# LED_Driver_-_1.net
KiCad netlist of a schematic drawn in Altium Designer
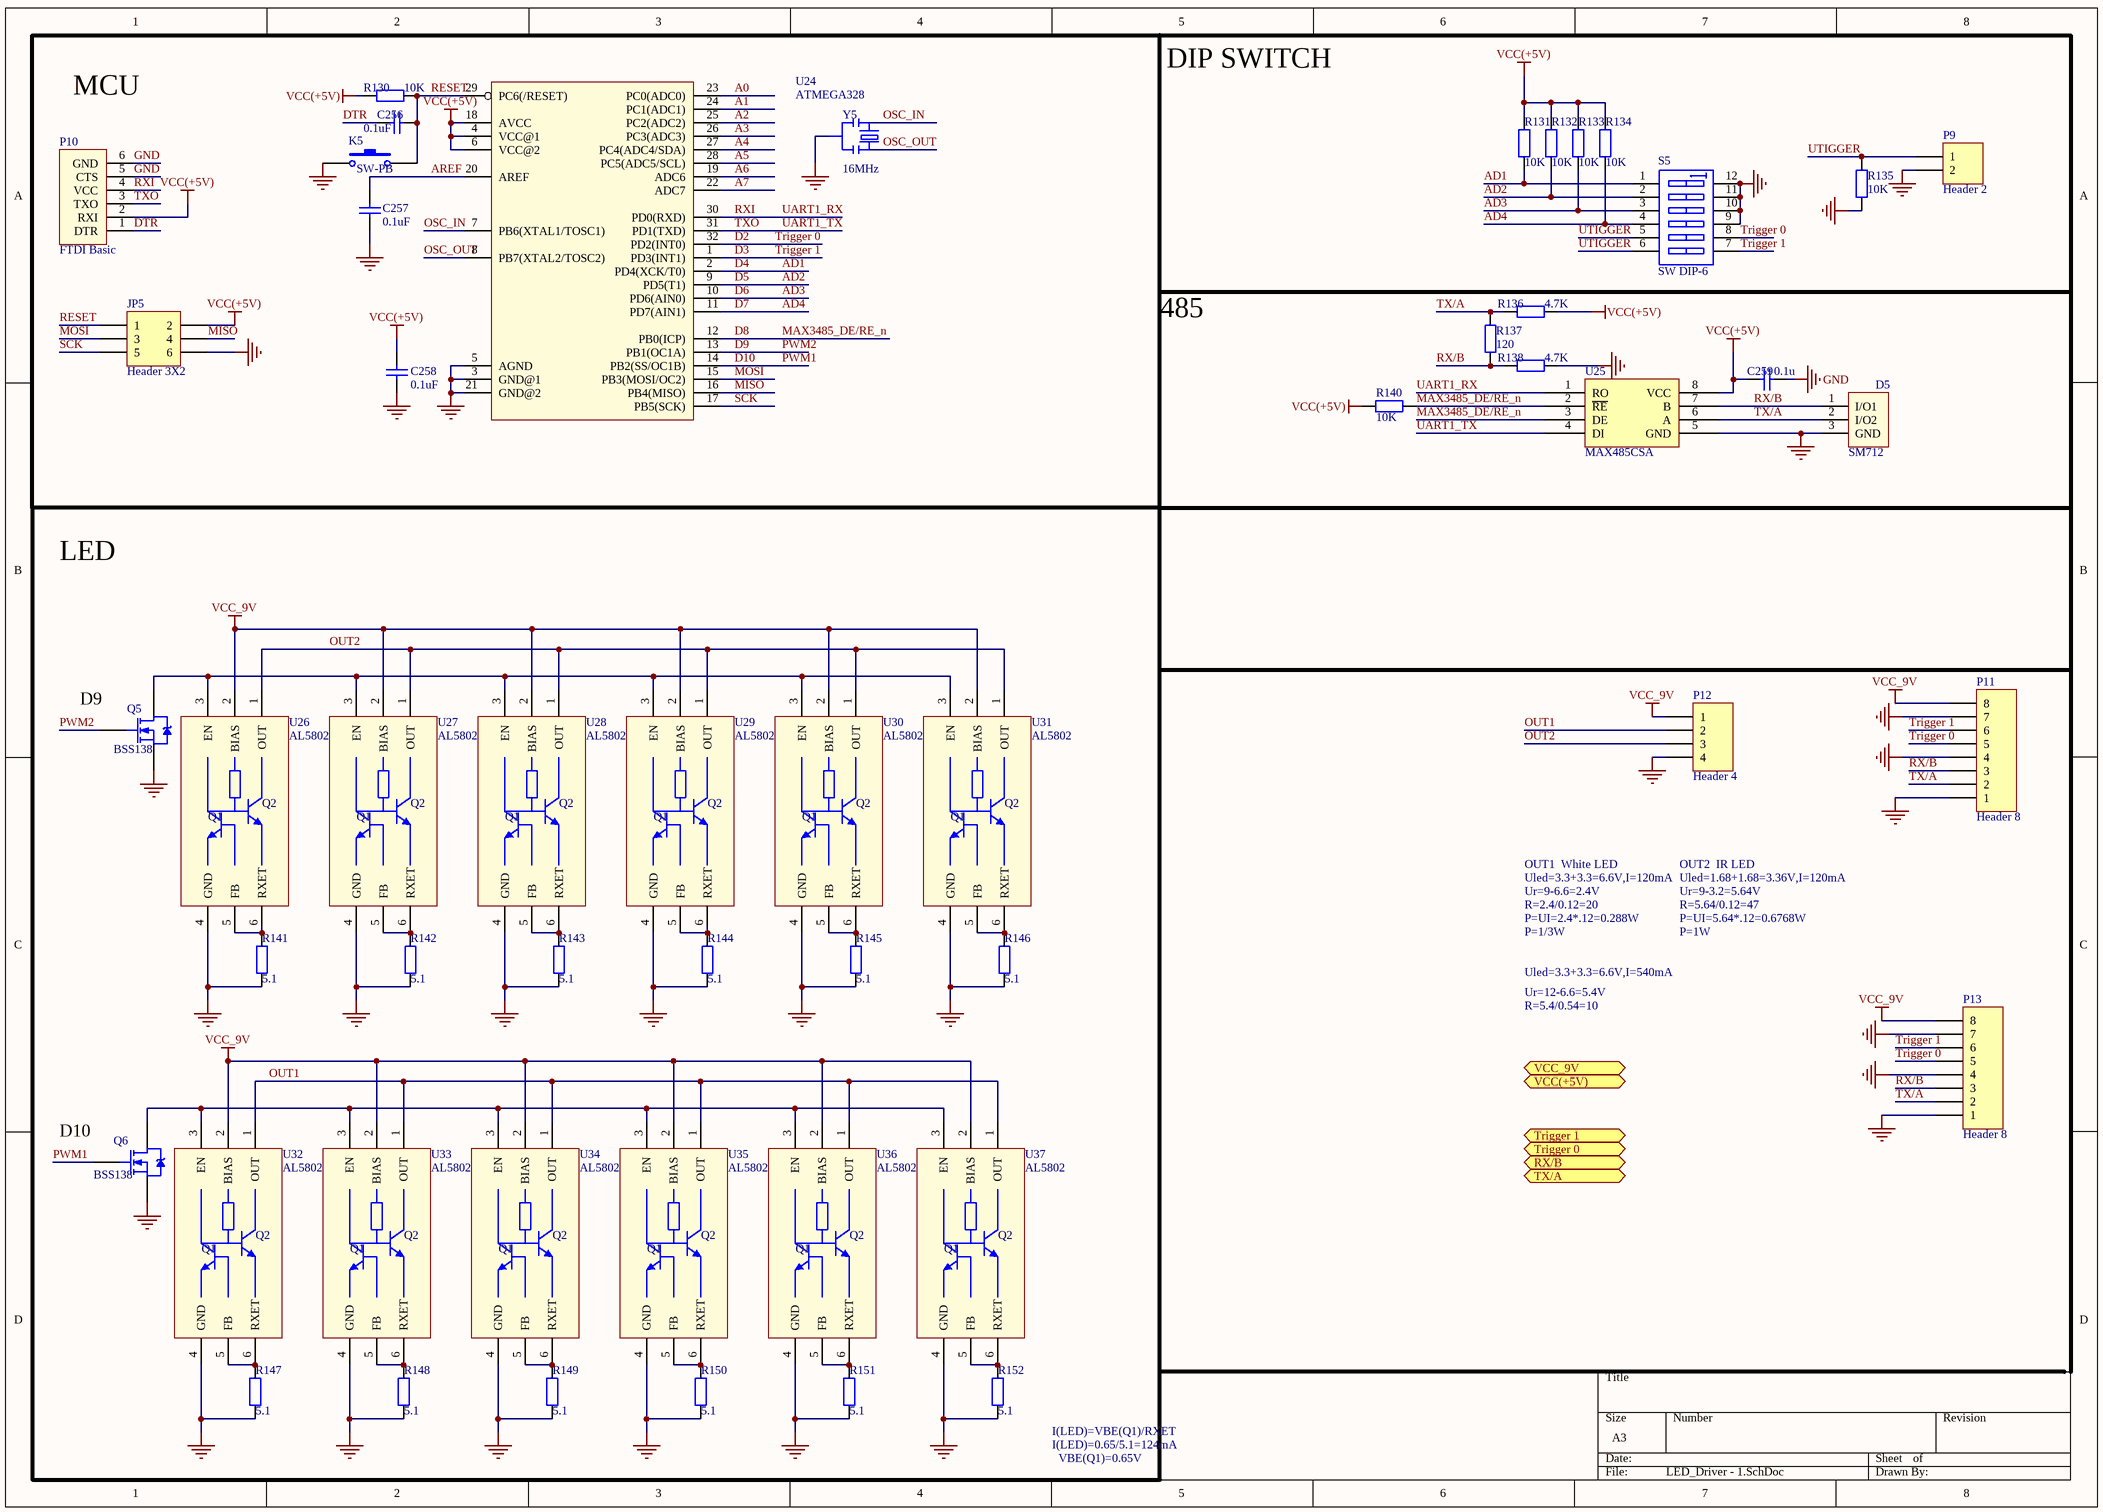
[diagram p0: LED_Driver - 1.SchDoc]

(export (version "E")
  (design (tool "Eeschema 10.0.6"))
  (components
    (comp (ref "C256")
      (value "0.1uF")
      (footprint "C0603")
      (description "Capacitor")
      (fields (field (name "IPARTNUMBER") "C100nF25V10%X7R") (field (name "VOLTAGE") "25V"))
      (libsource (lib "Schlib1") (part "CAP SMT C100nF25V10%X7R"))
    )
    (comp (ref "C257")
      (value "0.1uF")
      (footprint "C0603")
      (description "Capacitor")
      (fields (field (name "IPARTNUMBER") "C100nF25V10%X7R") (field (name "VOLTAGE") "25V"))
      (libsource (lib "Schlib1") (part "CAP SMT C100nF25V10%X7R"))
    )
    (comp (ref "C258")
      (value "0.1uF")
      (footprint "C0603")
      (description "Capacitor")
      (fields (field (name "IPARTNUMBER") "C100nF25V10%X7R") (field (name "VOLTAGE") "25V"))
      (libsource (lib "Schlib1") (part "CAP SMT C100nF25V10%X7R"))
    )
    (comp (ref "C259")
      (value "0.1u")
      (footprint "C0603")
      (description "Capacitor")
      (fields (field (name "PUBLISHER") "Altium Limited"))
      (libsource (lib "Miscellaneous Devices") (part "Cap"))
    )
    (comp (ref "D5")
      (value "SM712")
      (footprint "SOT23-3")
      (libsource (lib "STM32F4_CAM V2.0") (part "SM712"))
    )
    (comp (ref "JP5")
      (value "Header 3X2")
      (footprint "MHDR1X6")
      (description "Header, 3-Pin, Dual row")
      (fields (field (name "PUBLISHER") "Altium Limited"))
      (libsource (lib "Miscellaneous Connectors") (part "Header 3X2"))
    )
    (comp (ref "K5")
      (value "SW-PB")
      (footprint "157SW")
      (description "Switch")
      (fields (field (name "PUBLISHER") "Altium Limited"))
      (libsource (lib "Miscellaneous Devices") (part "SW-PB"))
    )
    (comp (ref "P9")
      (value "Header 2")
      (footprint "HDR1X2")
      (description "Header, 2-Pin")
      (fields (field (name "PUBLISHER") "Altium Limited"))
      (libsource (lib "Miscellaneous Connectors") (part "Header 2"))
    )
    (comp (ref "P10")
      (value "FTDI Basic")
      (footprint "MHDR1X6")
      (libsource (lib "PCB_Project1") (part "ARDUINO_SERIAL_PROGRAMPTH"))
    )
    (comp (ref "P11")
      (value "Header 8")
      (footprint "SH_1.25MM*8")
      (description "Header, 8-Pin")
      (fields (field (name "PUBLISHER") "Altium Limited"))
      (libsource (lib "Miscellaneous Connectors") (part "Header 8"))
    )
    (comp (ref "P12")
      (value "Header 4")
      (footprint "SMT_1.25MM*4")
      (description "Header, 4-Pin")
      (fields (field (name "PUBLISHER") "Altium Limited"))
      (libsource (lib "Miscellaneous Connectors") (part "Header 4"))
    )
    (comp (ref "P13")
      (value "Header 8")
      (footprint "SH_1.25MM*8")
      (description "Header, 8-Pin")
      (fields (field (name "PUBLISHER") "Altium Limited"))
      (libsource (lib "Miscellaneous Connectors") (part "Header 8"))
    )
    (comp (ref "Q5")
      (value "BSS138")
      (footprint "SOT-23 (Standard)")
      (fields
        (field (name "MANUFACTURER") "Fairchild Semiconductor")
        (field (name "MANUFACTURER PART NUMBER") "BSS123")
      )
      (libsource (lib "Miscellaneous_Devices") (part "NMOS"))
    )
    (comp (ref "Q6")
      (value "BSS138")
      (footprint "SOT-23 (Standard)")
      (fields
        (field (name "MANUFACTURER") "Fairchild Semiconductor")
        (field (name "MANUFACTURER PART NUMBER") "BSS123")
      )
      (libsource (lib "Miscellaneous_Devices") (part "NMOS"))
    )
    (comp (ref "R130")
      (value "10K")
      (footprint "R0603")
      (description "Resistor")
      (libsource (lib "") (part "Res2_2"))
    )
    (comp (ref "R131")
      (value "10K")
      (footprint "R0603")
      (description "Resistor")
      (libsource (lib "") (part "Res2_1"))
    )
    (comp (ref "R132")
      (value "10K")
      (footprint "R0603")
      (description "Resistor")
      (libsource (lib "") (part "Res2_1"))
    )
    (comp (ref "R133")
      (value "10K")
      (footprint "R0603")
      (description "Resistor")
      (libsource (lib "") (part "Res2_1"))
    )
    (comp (ref "R134")
      (value "10K")
      (footprint "R0603")
      (description "Resistor")
      (libsource (lib "") (part "Res2_1"))
    )
    (comp (ref "R135")
      (value "10K")
      (footprint "R0603")
      (description "Resistor")
      (fields (field (name "PUBLISHER") "Altium Limited"))
      (libsource (lib "Miscellaneous Devices") (part "Res2"))
    )
    (comp (ref "R136")
      (value "4.7K")
      (footprint "R0603")
      (description "Resistor")
      (libsource (lib "DM642") (part "Res2"))
    )
    (comp (ref "R137")
      (value "120")
      (footprint "R0603")
      (description "Resistor")
      (libsource (lib "") (part "Res2_1"))
    )
    (comp (ref "R138")
      (value "4.7K")
      (footprint "R0603")
      (description "Resistor")
      (libsource (lib "DM642") (part "Res2"))
    )
    (comp (ref "R140")
      (value "10K")
      (footprint "R0603")
      (description "Resistor")
      (libsource (lib "DM642") (part "Res2"))
    )
    (comp (ref "R141")
      (value "5.1")
      (footprint "R0603")
      (description "Resistor")
      (libsource (lib "") (part "Res2_1"))
    )
    (comp (ref "R142")
      (value "5.1")
      (footprint "R0603")
      (description "Resistor")
      (libsource (lib "") (part "Res2_1"))
    )
    (comp (ref "R143")
      (value "5.1")
      (footprint "R0603")
      (description "Resistor")
      (libsource (lib "") (part "Res2_1"))
    )
    (comp (ref "R144")
      (value "5.1")
      (footprint "R0603")
      (description "Resistor")
      (libsource (lib "") (part "Res2_1"))
    )
    (comp (ref "R145")
      (value "5.1")
      (footprint "R0603")
      (description "Resistor")
      (libsource (lib "") (part "Res2_1"))
    )
    (comp (ref "R146")
      (value "5.1")
      (footprint "R0603")
      (description "Resistor")
      (libsource (lib "") (part "Res2_1"))
    )
    (comp (ref "R147")
      (value "5.1")
      (footprint "R0603")
      (description "Resistor")
      (libsource (lib "") (part "Res2_1"))
    )
    (comp (ref "R148")
      (value "5.1")
      (footprint "R0603")
      (description "Resistor")
      (libsource (lib "") (part "Res2_1"))
    )
    (comp (ref "R149")
      (value "5.1")
      (footprint "R0603")
      (description "Resistor")
      (libsource (lib "") (part "Res2_1"))
    )
    (comp (ref "R150")
      (value "5.1")
      (footprint "R0603")
      (description "Resistor")
      (libsource (lib "") (part "Res2_1"))
    )
    (comp (ref "R151")
      (value "5.1")
      (footprint "R0603")
      (description "Resistor")
      (libsource (lib "") (part "Res2_1"))
    )
    (comp (ref "R152")
      (value "5.1")
      (footprint "R0603")
      (description "Resistor")
      (libsource (lib "") (part "Res2_1"))
    )
    (comp (ref "S5")
      (value "SW DIP-6")
      (footprint "DIP_SW_6WAY_SMD")
      (description "DIP Switch, 6 Position, SPST")
      (fields (field (name "PUBLISHER") "Altium Limited"))
      (libsource (lib "Miscellaneous Devices") (part "SW DIP-6"))
    )
    (comp (ref "U24")
      (value "ATMEGA328")
      (footprint "TQFP32-08")
      (libsource (lib "PCB_Project1") (part "ATMEGA168"))
    )
    (comp (ref "U25")
      (value "MAX485CSA")
      (footprint "SOIC-8")
      (libsource (lib "STM32F4_CAM V1.2") (part "MAX3485CSA"))
    )
    (comp (ref "U26") (value "AL5802") (footprint "SOT26") (libsource (lib "LED") (part "AL5802")))
    (comp (ref "U27") (value "AL5802") (footprint "SOT26") (libsource (lib "LED") (part "AL5802")))
    (comp (ref "U28") (value "AL5802") (footprint "SOT26") (libsource (lib "LED") (part "AL5802")))
    (comp (ref "U29") (value "AL5802") (footprint "SOT26") (libsource (lib "LED") (part "AL5802")))
    (comp (ref "U30") (value "AL5802") (footprint "SOT26") (libsource (lib "LED") (part "AL5802")))
    (comp (ref "U31") (value "AL5802") (footprint "SOT26") (libsource (lib "LED") (part "AL5802")))
    (comp (ref "U32") (value "AL5802") (footprint "SOT26") (libsource (lib "LED") (part "AL5802")))
    (comp (ref "U33") (value "AL5802") (footprint "SOT26") (libsource (lib "LED") (part "AL5802")))
    (comp (ref "U34") (value "AL5802") (footprint "SOT26") (libsource (lib "LED") (part "AL5802")))
    (comp (ref "U35") (value "AL5802") (footprint "SOT26") (libsource (lib "LED") (part "AL5802")))
    (comp (ref "U36") (value "AL5802") (footprint "SOT26") (libsource (lib "LED") (part "AL5802")))
    (comp (ref "U37") (value "AL5802") (footprint "SOT26") (libsource (lib "LED") (part "AL5802")))
    (comp (ref "Y5")
      (value "16MHz")
      (footprint "RESONATOR-SMD")
      (libsource (lib "SparkFun") (part "RESONATORSMD"))
    )
  )
  (nets
    (net (code "1") (name "/A0") (class "Default")
      (node (ref "U24") (pin "23") (pinfunction "PC0(ADC0)_23") (pintype "passive"))
    )
    (net (code "2") (name "/A1") (class "Default")
      (node (ref "U24") (pin "24") (pinfunction "PC1(ADC1)_24") (pintype "passive"))
    )
    (net (code "3") (name "/A2") (class "Default")
      (node (ref "U24") (pin "25") (pinfunction "PC2(ADC2)_25") (pintype "passive"))
    )
    (net (code "4") (name "/A3") (class "Default")
      (node (ref "U24") (pin "26") (pinfunction "PC3(ADC3)_26") (pintype "passive"))
    )
    (net (code "5") (name "/A4") (class "Default")
      (node (ref "U24") (pin "27") (pinfunction "PC4(ADC4/SDA)_27") (pintype "passive"))
    )
    (net (code "6") (name "/A5") (class "Default")
      (node (ref "U24") (pin "28") (pinfunction "PC5(ADC5/SCL)_28") (pintype "passive"))
    )
    (net (code "7") (name "/A6") (class "Default")
      (node (ref "U24") (pin "19") (pinfunction "ADC6_19") (pintype "passive"))
    )
    (net (code "8") (name "/A7") (class "Default")
      (node (ref "U24") (pin "22") (pinfunction "ADC7_22") (pintype "passive"))
    )
    (net (code "9") (name "/AD1") (class "Default")
      (node (ref "R131") (pin "2") (pinfunction "2_2") (pintype "passive"))
      (node (ref "S5") (pin "1") (pinfunction "A1_1") (pintype "passive"))
      (node (ref "U24") (pin "2") (pinfunction "PD4(XCK/T0)_2") (pintype "passive"))
    )
    (net (code "10") (name "/AD2") (class "Default")
      (node (ref "R132") (pin "2") (pinfunction "2_2") (pintype "passive"))
      (node (ref "S5") (pin "2") (pinfunction "A2_2") (pintype "passive"))
      (node (ref "U24") (pin "9") (pinfunction "PD5(T1)_9") (pintype "passive"))
    )
    (net (code "11") (name "/AD3") (class "Default")
      (node (ref "R133") (pin "2") (pinfunction "2_2") (pintype "passive"))
      (node (ref "S5") (pin "3") (pinfunction "A3_3") (pintype "passive"))
      (node (ref "U24") (pin "10") (pinfunction "PD6(AIN0)_10") (pintype "passive"))
    )
    (net (code "12") (name "/AD4") (class "Default")
      (node (ref "R134") (pin "2") (pinfunction "2_2") (pintype "passive"))
      (node (ref "S5") (pin "4") (pinfunction "A4_4") (pintype "passive"))
      (node (ref "U24") (pin "11") (pinfunction "PD7(AIN1)_11") (pintype "passive"))
    )
    (net (code "13") (name "/AREF") (class "Default")
      (node (ref "C257") (pin "2") (pinfunction "2_2") (pintype "passive"))
      (node (ref "U24") (pin "20") (pinfunction "AREF_20") (pintype "passive"))
    )
    (net (code "14") (name "/D2") (class "Default")
      (node (ref "P11") (pin "5") (pinfunction "5_5") (pintype "passive"))
      (node (ref "P13") (pin "5") (pinfunction "5_5") (pintype "passive"))
      (node (ref "S5") (pin "8") (pinfunction "B5_8") (pintype "passive"))
      (node (ref "U24") (pin "32") (pinfunction "PD2(INT0)_32") (pintype "passive"))
    )
    (net (code "15") (name "/D3") (class "Default")
      (node (ref "P11") (pin "6") (pinfunction "6_6") (pintype "passive"))
      (node (ref "P13") (pin "6") (pinfunction "6_6") (pintype "passive"))
      (node (ref "S5") (pin "7") (pinfunction "B6_7") (pintype "passive"))
      (node (ref "U24") (pin "1") (pinfunction "PD3(INT1)_1") (pintype "passive"))
    )
    (net (code "16") (name "/D8") (class "Default")
      (node (ref "R140") (pin "1") (pinfunction "1_1") (pintype "passive"))
      (node (ref "U24") (pin "12") (pinfunction "PB0(ICP)_12") (pintype "passive"))
      (node (ref "U25") (pin "2") (pinfunction "~{RE}_2") (pintype "passive"))
      (node (ref "U25") (pin "3") (pinfunction "DE_3") (pintype "passive"))
    )
    (net (code "17") (name "/D9") (class "Default")
      (node (ref "Q5") (pin "G") (pinfunction "G_G") (pintype "passive"))
      (node (ref "U24") (pin "13") (pinfunction "PB1(OC1A)_13") (pintype "passive"))
    )
    (net (code "18") (name "/D10") (class "Default")
      (node (ref "Q6") (pin "G") (pinfunction "G_G") (pintype "passive"))
      (node (ref "U24") (pin "14") (pinfunction "PB2(SS/OC1B)_14") (pintype "passive"))
    )
    (net (code "19") (name "/DTR") (class "Default")
      (node (ref "C256") (pin "1") (pinfunction "1_1") (pintype "passive"))
      (node (ref "P10") (pin "1") (pinfunction "DTR_1") (pintype "passive"))
    )
    (net (code "20") (name "/MISO") (class "Default")
      (node (ref "JP5") (pin "4") (pinfunction "4_4") (pintype "passive"))
      (node (ref "U24") (pin "16") (pinfunction "PB4(MISO)_16") (pintype "passive"))
    )
    (net (code "21") (name "/MOSI") (class "Default")
      (node (ref "JP5") (pin "3") (pinfunction "3_3") (pintype "passive"))
      (node (ref "U24") (pin "15") (pinfunction "PB3(MOSI/OC2)_15") (pintype "passive"))
    )
    (net (code "22") (name "/OSC_IN") (class "Default")
      (node (ref "U24") (pin "7") (pinfunction "PB6(XTAL1/TOSC1)_7") (pintype "passive"))
      (node (ref "Y5") (pin "3") (pinfunction "3_3") (pintype "passive"))
    )
    (net (code "23") (name "/OSC_OUT") (class "Default")
      (node (ref "U24") (pin "8") (pinfunction "PB7(XTAL2/TOSC2)_8") (pintype "passive"))
      (node (ref "Y5") (pin "1") (pinfunction "1_1") (pintype "passive"))
    )
    (net (code "24") (name "/OUT1") (class "Default")
      (node (ref "P12") (pin "2") (pinfunction "2_2") (pintype "passive"))
      (node (ref "U32") (pin "1") (pinfunction "OUT_1") (pintype "passive"))
      (node (ref "U33") (pin "1") (pinfunction "OUT_1") (pintype "passive"))
      (node (ref "U34") (pin "1") (pinfunction "OUT_1") (pintype "passive"))
      (node (ref "U35") (pin "1") (pinfunction "OUT_1") (pintype "passive"))
      (node (ref "U36") (pin "1") (pinfunction "OUT_1") (pintype "passive"))
      (node (ref "U37") (pin "1") (pinfunction "OUT_1") (pintype "passive"))
    )
    (net (code "25") (name "/OUT2") (class "Default")
      (node (ref "P12") (pin "3") (pinfunction "3_3") (pintype "passive"))
      (node (ref "U26") (pin "1") (pinfunction "OUT_1") (pintype "passive"))
      (node (ref "U27") (pin "1") (pinfunction "OUT_1") (pintype "passive"))
      (node (ref "U28") (pin "1") (pinfunction "OUT_1") (pintype "passive"))
      (node (ref "U29") (pin "1") (pinfunction "OUT_1") (pintype "passive"))
      (node (ref "U30") (pin "1") (pinfunction "OUT_1") (pintype "passive"))
      (node (ref "U31") (pin "1") (pinfunction "OUT_1") (pintype "passive"))
    )
    (net (code "26") (name "/RESET") (class "Default")
      (node (ref "C256") (pin "2") (pinfunction "2_2") (pintype "passive"))
      (node (ref "JP5") (pin "1") (pinfunction "1_1") (pintype "passive"))
      (node (ref "K5") (pin "2") (pinfunction "2_2") (pintype "passive"))
      (node (ref "R130") (pin "2") (pinfunction "2_2") (pintype "passive"))
      (node (ref "U24") (pin "29") (pinfunction "PC6(/RESET)_29") (pintype "passive"))
    )
    (net (code "27") (name "/RXI") (class "Default")
      (node (ref "P10") (pin "4") (pinfunction "VCC_4") (pintype "passive"))
      (node (ref "U24") (pin "30") (pinfunction "PD0(RXD)_30") (pintype "passive"))
      (node (ref "U25") (pin "1") (pinfunction "RO_1") (pintype "passive"))
    )
    (net (code "28") (name "/RX{slash}B") (class "Default")
      (node (ref "D5") (pin "1") (pinfunction "I/O1_1") (pintype "passive"))
      (node (ref "P11") (pin "3") (pinfunction "3_3") (pintype "passive"))
      (node (ref "P13") (pin "3") (pinfunction "3_3") (pintype "passive"))
      (node (ref "R137") (pin "2") (pinfunction "2_2") (pintype "passive"))
      (node (ref "R138") (pin "2") (pinfunction "2_2") (pintype "passive"))
      (node (ref "U25") (pin "7") (pinfunction "B_7") (pintype "passive"))
    )
    (net (code "29") (name "/SCK") (class "Default")
      (node (ref "JP5") (pin "5") (pinfunction "5_5") (pintype "passive"))
      (node (ref "U24") (pin "17") (pinfunction "PB5(SCK)_17") (pintype "passive"))
    )
    (net (code "30") (name "/TXO") (class "Default")
      (node (ref "P10") (pin "3") (pinfunction "TXO_3") (pintype "passive"))
      (node (ref "U24") (pin "31") (pinfunction "PD1(TXD)_31") (pintype "passive"))
      (node (ref "U25") (pin "4") (pinfunction "DI_4") (pintype "passive"))
    )
    (net (code "31") (name "/TX{slash}A") (class "Default")
      (node (ref "D5") (pin "2") (pinfunction "I/O2_2") (pintype "passive"))
      (node (ref "P11") (pin "2") (pinfunction "2_2") (pintype "passive"))
      (node (ref "P13") (pin "2") (pinfunction "2_2") (pintype "passive"))
      (node (ref "R136") (pin "2") (pinfunction "2_2") (pintype "passive"))
      (node (ref "R137") (pin "1") (pinfunction "1_1") (pintype "passive"))
      (node (ref "U25") (pin "6") (pinfunction "A_6") (pintype "passive"))
    )
    (net (code "32") (name "/UTIGGER") (class "Default")
      (node (ref "P9") (pin "1") (pinfunction "1_1") (pintype "passive"))
      (node (ref "R135") (pin "2") (pinfunction "2_2") (pintype "passive"))
      (node (ref "S5") (pin "5") (pinfunction "A5_5") (pintype "passive"))
      (node (ref "S5") (pin "6") (pinfunction "A6_6") (pintype "passive"))
    )
    (net (code "33") (name "GND") (class "Default")
      (node (ref "C257") (pin "1") (pinfunction "1_1") (pintype "passive"))
      (node (ref "C258") (pin "2") (pinfunction "2_2") (pintype "passive"))
      (node (ref "C259") (pin "1") (pinfunction "1_1") (pintype "passive"))
      (node (ref "D5") (pin "3") (pinfunction "GND_3") (pintype "passive"))
      (node (ref "JP5") (pin "6") (pinfunction "6_6") (pintype "passive"))
      (node (ref "K5") (pin "1") (pinfunction "1_1") (pintype "passive"))
      (node (ref "P10") (pin "5") (pinfunction "CTS_5") (pintype "passive"))
      (node (ref "P10") (pin "6") (pinfunction "GND_6") (pintype "passive"))
      (node (ref "P11") (pin "1") (pinfunction "1_1") (pintype "passive"))
      (node (ref "P11") (pin "4") (pinfunction "4_4") (pintype "passive"))
      (node (ref "P11") (pin "7") (pinfunction "7_7") (pintype "passive"))
      (node (ref "P12") (pin "4") (pinfunction "4_4") (pintype "passive"))
      (node (ref "P13") (pin "1") (pinfunction "1_1") (pintype "passive"))
      (node (ref "P13") (pin "4") (pinfunction "4_4") (pintype "passive"))
      (node (ref "P13") (pin "7") (pinfunction "7_7") (pintype "passive"))
      (node (ref "P9") (pin "2") (pinfunction "2_2") (pintype "passive"))
      (node (ref "Q5") (pin "S") (pinfunction "S_S") (pintype "passive"))
      (node (ref "Q6") (pin "S") (pinfunction "S_S") (pintype "passive"))
      (node (ref "R135") (pin "1") (pinfunction "1_1") (pintype "passive"))
      (node (ref "R138") (pin "1") (pinfunction "1_1") (pintype "passive"))
      (node (ref "R141") (pin "2") (pinfunction "2_2") (pintype "passive"))
      (node (ref "R142") (pin "2") (pinfunction "2_2") (pintype "passive"))
      (node (ref "R143") (pin "2") (pinfunction "2_2") (pintype "passive"))
      (node (ref "R144") (pin "2") (pinfunction "2_2") (pintype "passive"))
      (node (ref "R145") (pin "2") (pinfunction "2_2") (pintype "passive"))
      (node (ref "R146") (pin "2") (pinfunction "2_2") (pintype "passive"))
      (node (ref "R147") (pin "2") (pinfunction "2_2") (pintype "passive"))
      (node (ref "R148") (pin "2") (pinfunction "2_2") (pintype "passive"))
      (node (ref "R149") (pin "2") (pinfunction "2_2") (pintype "passive"))
      (node (ref "R150") (pin "2") (pinfunction "2_2") (pintype "passive"))
      (node (ref "R151") (pin "2") (pinfunction "2_2") (pintype "passive"))
      (node (ref "R152") (pin "2") (pinfunction "2_2") (pintype "passive"))
      (node (ref "S5") (pin "10") (pinfunction "B3_10") (pintype "passive"))
      (node (ref "S5") (pin "11") (pinfunction "B2_11") (pintype "passive"))
      (node (ref "S5") (pin "12") (pinfunction "B1_12") (pintype "passive"))
      (node (ref "S5") (pin "9") (pinfunction "B4_9") (pintype "passive"))
      (node (ref "U24") (pin "21") (pinfunction "GND@2_21") (pintype "passive"))
      (node (ref "U24") (pin "3") (pinfunction "GND@1_3") (pintype "passive"))
      (node (ref "U24") (pin "5") (pinfunction "AGND_5") (pintype "passive"))
      (node (ref "U25") (pin "5") (pinfunction "GND_5") (pintype "passive"))
      (node (ref "U26") (pin "4") (pinfunction "GND_4") (pintype "passive"))
      (node (ref "U27") (pin "4") (pinfunction "GND_4") (pintype "passive"))
      (node (ref "U28") (pin "4") (pinfunction "GND_4") (pintype "passive"))
      (node (ref "U29") (pin "4") (pinfunction "GND_4") (pintype "passive"))
      (node (ref "U30") (pin "4") (pinfunction "GND_4") (pintype "passive"))
      (node (ref "U31") (pin "4") (pinfunction "GND_4") (pintype "passive"))
      (node (ref "U32") (pin "4") (pinfunction "GND_4") (pintype "passive"))
      (node (ref "U33") (pin "4") (pinfunction "GND_4") (pintype "passive"))
      (node (ref "U34") (pin "4") (pinfunction "GND_4") (pintype "passive"))
      (node (ref "U35") (pin "4") (pinfunction "GND_4") (pintype "passive"))
      (node (ref "U36") (pin "4") (pinfunction "GND_4") (pintype "passive"))
      (node (ref "U37") (pin "4") (pinfunction "GND_4") (pintype "passive"))
      (node (ref "Y5") (pin "2") (pinfunction "2_2") (pintype "passive"))
    )
    (net (code "34") (name "Net-(U26-EN)") (class "Default")
      (node (ref "Q5") (pin "D") (pinfunction "D_D") (pintype "passive"))
      (node (ref "U26") (pin "3") (pinfunction "EN_3") (pintype "passive"))
      (node (ref "U27") (pin "3") (pinfunction "EN_3") (pintype "passive"))
      (node (ref "U28") (pin "3") (pinfunction "EN_3") (pintype "passive"))
      (node (ref "U29") (pin "3") (pinfunction "EN_3") (pintype "passive"))
      (node (ref "U30") (pin "3") (pinfunction "EN_3") (pintype "passive"))
      (node (ref "U31") (pin "3") (pinfunction "EN_3") (pintype "passive"))
    )
    (net (code "35") (name "Net-(U26-FB)") (class "Default")
      (node (ref "R141") (pin "1") (pinfunction "1_1") (pintype "passive"))
      (node (ref "U26") (pin "5") (pinfunction "FB_5") (pintype "passive"))
      (node (ref "U26") (pin "6") (pinfunction "RXET_6") (pintype "passive"))
    )
    (net (code "36") (name "Net-(U27-FB)") (class "Default")
      (node (ref "R142") (pin "1") (pinfunction "1_1") (pintype "passive"))
      (node (ref "U27") (pin "5") (pinfunction "FB_5") (pintype "passive"))
      (node (ref "U27") (pin "6") (pinfunction "RXET_6") (pintype "passive"))
    )
    (net (code "37") (name "Net-(U28-FB)") (class "Default")
      (node (ref "R143") (pin "1") (pinfunction "1_1") (pintype "passive"))
      (node (ref "U28") (pin "5") (pinfunction "FB_5") (pintype "passive"))
      (node (ref "U28") (pin "6") (pinfunction "RXET_6") (pintype "passive"))
    )
    (net (code "38") (name "Net-(U29-FB)") (class "Default")
      (node (ref "R144") (pin "1") (pinfunction "1_1") (pintype "passive"))
      (node (ref "U29") (pin "5") (pinfunction "FB_5") (pintype "passive"))
      (node (ref "U29") (pin "6") (pinfunction "RXET_6") (pintype "passive"))
    )
    (net (code "39") (name "Net-(U30-FB)") (class "Default")
      (node (ref "R145") (pin "1") (pinfunction "1_1") (pintype "passive"))
      (node (ref "U30") (pin "5") (pinfunction "FB_5") (pintype "passive"))
      (node (ref "U30") (pin "6") (pinfunction "RXET_6") (pintype "passive"))
    )
    (net (code "40") (name "Net-(U31-FB)") (class "Default")
      (node (ref "R146") (pin "1") (pinfunction "1_1") (pintype "passive"))
      (node (ref "U31") (pin "5") (pinfunction "FB_5") (pintype "passive"))
      (node (ref "U31") (pin "6") (pinfunction "RXET_6") (pintype "passive"))
    )
    (net (code "41") (name "Net-(U32-EN)") (class "Default")
      (node (ref "Q6") (pin "D") (pinfunction "D_D") (pintype "passive"))
      (node (ref "U32") (pin "3") (pinfunction "EN_3") (pintype "passive"))
      (node (ref "U33") (pin "3") (pinfunction "EN_3") (pintype "passive"))
      (node (ref "U34") (pin "3") (pinfunction "EN_3") (pintype "passive"))
      (node (ref "U35") (pin "3") (pinfunction "EN_3") (pintype "passive"))
      (node (ref "U36") (pin "3") (pinfunction "EN_3") (pintype "passive"))
      (node (ref "U37") (pin "3") (pinfunction "EN_3") (pintype "passive"))
    )
    (net (code "42") (name "Net-(U32-FB)") (class "Default")
      (node (ref "R147") (pin "1") (pinfunction "1_1") (pintype "passive"))
      (node (ref "U32") (pin "5") (pinfunction "FB_5") (pintype "passive"))
      (node (ref "U32") (pin "6") (pinfunction "RXET_6") (pintype "passive"))
    )
    (net (code "43") (name "Net-(U33-FB)") (class "Default")
      (node (ref "R148") (pin "1") (pinfunction "1_1") (pintype "passive"))
      (node (ref "U33") (pin "5") (pinfunction "FB_5") (pintype "passive"))
      (node (ref "U33") (pin "6") (pinfunction "RXET_6") (pintype "passive"))
    )
    (net (code "44") (name "Net-(U34-FB)") (class "Default")
      (node (ref "R149") (pin "1") (pinfunction "1_1") (pintype "passive"))
      (node (ref "U34") (pin "5") (pinfunction "FB_5") (pintype "passive"))
      (node (ref "U34") (pin "6") (pinfunction "RXET_6") (pintype "passive"))
    )
    (net (code "45") (name "Net-(U35-FB)") (class "Default")
      (node (ref "R150") (pin "1") (pinfunction "1_1") (pintype "passive"))
      (node (ref "U35") (pin "5") (pinfunction "FB_5") (pintype "passive"))
      (node (ref "U35") (pin "6") (pinfunction "RXET_6") (pintype "passive"))
    )
    (net (code "46") (name "Net-(U36-FB)") (class "Default")
      (node (ref "R151") (pin "1") (pinfunction "1_1") (pintype "passive"))
      (node (ref "U36") (pin "5") (pinfunction "FB_5") (pintype "passive"))
      (node (ref "U36") (pin "6") (pinfunction "RXET_6") (pintype "passive"))
    )
    (net (code "47") (name "Net-(U37-FB)") (class "Default")
      (node (ref "R152") (pin "1") (pinfunction "1_1") (pintype "passive"))
      (node (ref "U37") (pin "5") (pinfunction "FB_5") (pintype "passive"))
      (node (ref "U37") (pin "6") (pinfunction "RXET_6") (pintype "passive"))
    )
    (net (code "48") (name "VCC(+5V)") (class "Default")
      (node (ref "C258") (pin "1") (pinfunction "1_1") (pintype "passive"))
      (node (ref "C259") (pin "2") (pinfunction "2_2") (pintype "passive"))
      (node (ref "JP5") (pin "2") (pinfunction "2_2") (pintype "passive"))
      (node (ref "P10") (pin "2") (pinfunction "RXI_2") (pintype "passive"))
      (node (ref "R130") (pin "1") (pinfunction "1_1") (pintype "passive"))
      (node (ref "R131") (pin "1") (pinfunction "1_1") (pintype "passive"))
      (node (ref "R132") (pin "1") (pinfunction "1_1") (pintype "passive"))
      (node (ref "R133") (pin "1") (pinfunction "1_1") (pintype "passive"))
      (node (ref "R134") (pin "1") (pinfunction "1_1") (pintype "passive"))
      (node (ref "R136") (pin "1") (pinfunction "1_1") (pintype "passive"))
      (node (ref "R140") (pin "2") (pinfunction "2_2") (pintype "passive"))
      (node (ref "U24") (pin "18") (pinfunction "AVCC_18") (pintype "passive"))
      (node (ref "U24") (pin "4") (pinfunction "VCC@1_4") (pintype "passive"))
      (node (ref "U24") (pin "6") (pinfunction "VCC@2_6") (pintype "passive"))
      (node (ref "U25") (pin "8") (pinfunction "VCC_8") (pintype "passive"))
    )
    (net (code "49") (name "VCC_9V") (class "Default")
      (node (ref "P11") (pin "8") (pinfunction "8_8") (pintype "passive"))
      (node (ref "P12") (pin "1") (pinfunction "1_1") (pintype "passive"))
      (node (ref "P13") (pin "8") (pinfunction "8_8") (pintype "passive"))
      (node (ref "U26") (pin "2") (pinfunction "BIAS_2") (pintype "passive"))
      (node (ref "U27") (pin "2") (pinfunction "BIAS_2") (pintype "passive"))
      (node (ref "U28") (pin "2") (pinfunction "BIAS_2") (pintype "passive"))
      (node (ref "U29") (pin "2") (pinfunction "BIAS_2") (pintype "passive"))
      (node (ref "U30") (pin "2") (pinfunction "BIAS_2") (pintype "passive"))
      (node (ref "U31") (pin "2") (pinfunction "BIAS_2") (pintype "passive"))
      (node (ref "U32") (pin "2") (pinfunction "BIAS_2") (pintype "passive"))
      (node (ref "U33") (pin "2") (pinfunction "BIAS_2") (pintype "passive"))
      (node (ref "U34") (pin "2") (pinfunction "BIAS_2") (pintype "passive"))
      (node (ref "U35") (pin "2") (pinfunction "BIAS_2") (pintype "passive"))
      (node (ref "U36") (pin "2") (pinfunction "BIAS_2") (pintype "passive"))
      (node (ref "U37") (pin "2") (pinfunction "BIAS_2") (pintype "passive"))
    )
  )
)
